# RL_PCB.net
KiCad netlist of a schematic drawn in EasyEDA
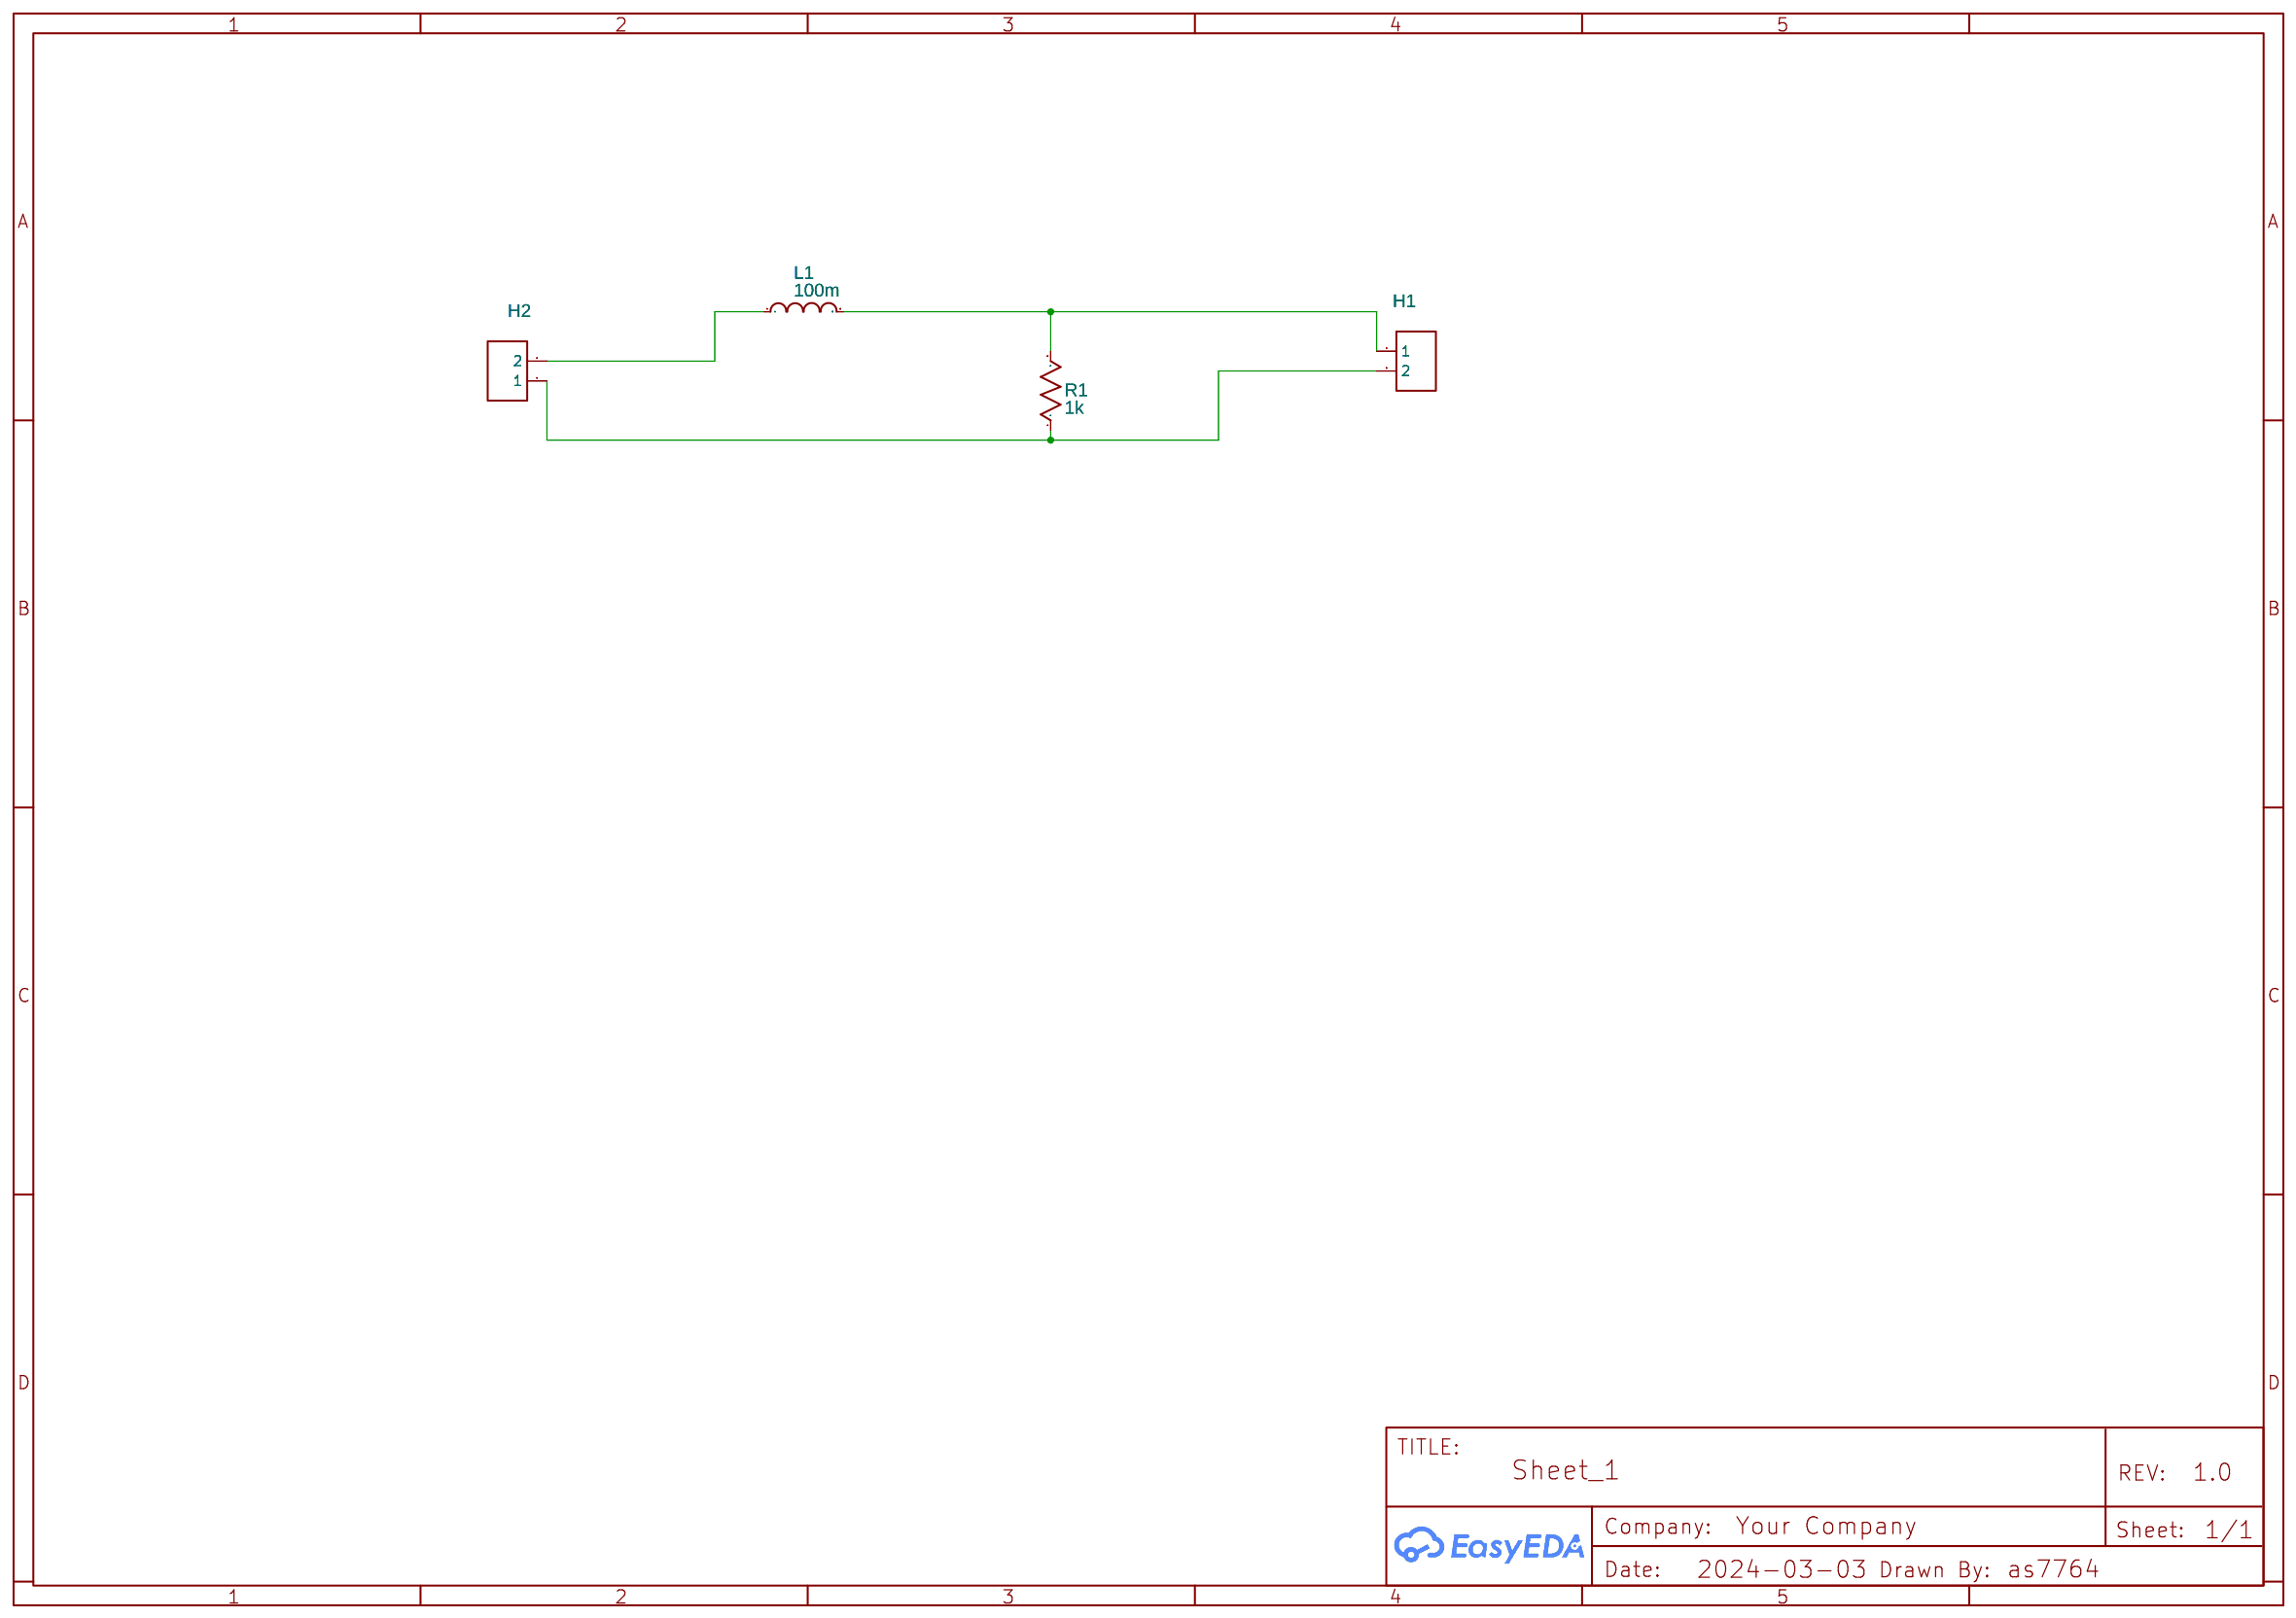
[diagram p0: schematic sheet]

(export (version "E")
  (design (tool "Eeschema 10.0.6"))
  (components
    (comp (ref "H1") (value "HDR-F-2.54_1x2") (libsource (lib "") (part "HDR-F-2.54_1x2")))
    (comp (ref "H2") (value "HDR-F-2.54_1x2") (libsource (lib "") (part "HDR-F-2.54_1x2_1")))
    (comp (ref "L1") (value "100m") (libsource (lib "") (part "L_AXIAL-0.4_US")))
    (comp (ref "R1") (value "1k") (libsource (lib "") (part "R_AXIAL-0.3_US")))
  )
  (nets
    (net (code "1") (name "Net-(H1-Pad1)") (class "Default")
      (node (ref "H1") (pin "1") (pinfunction "1_1") (pintype "input"))
      (node (ref "L1") (pin "2") (pinfunction "2_2") (pintype "unspecified"))
      (node (ref "R1") (pin "2") (pinfunction "2_2") (pintype "unspecified"))
    )
    (net (code "2") (name "Net-(H1-Pad2)") (class "Default")
      (node (ref "H1") (pin "2") (pinfunction "2_2") (pintype "input"))
      (node (ref "H2") (pin "1") (pinfunction "1_1") (pintype "input"))
      (node (ref "R1") (pin "1") (pinfunction "1_1") (pintype "unspecified"))
    )
    (net (code "3") (name "Net-(H2-Pad2)") (class "Default")
      (node (ref "H2") (pin "2") (pinfunction "2_2") (pintype "input"))
      (node (ref "L1") (pin "1") (pinfunction "1_1") (pintype "unspecified"))
    )
  )
)
